# mainboard.net
KiCad netlist of a schematic drawn in EAGLE
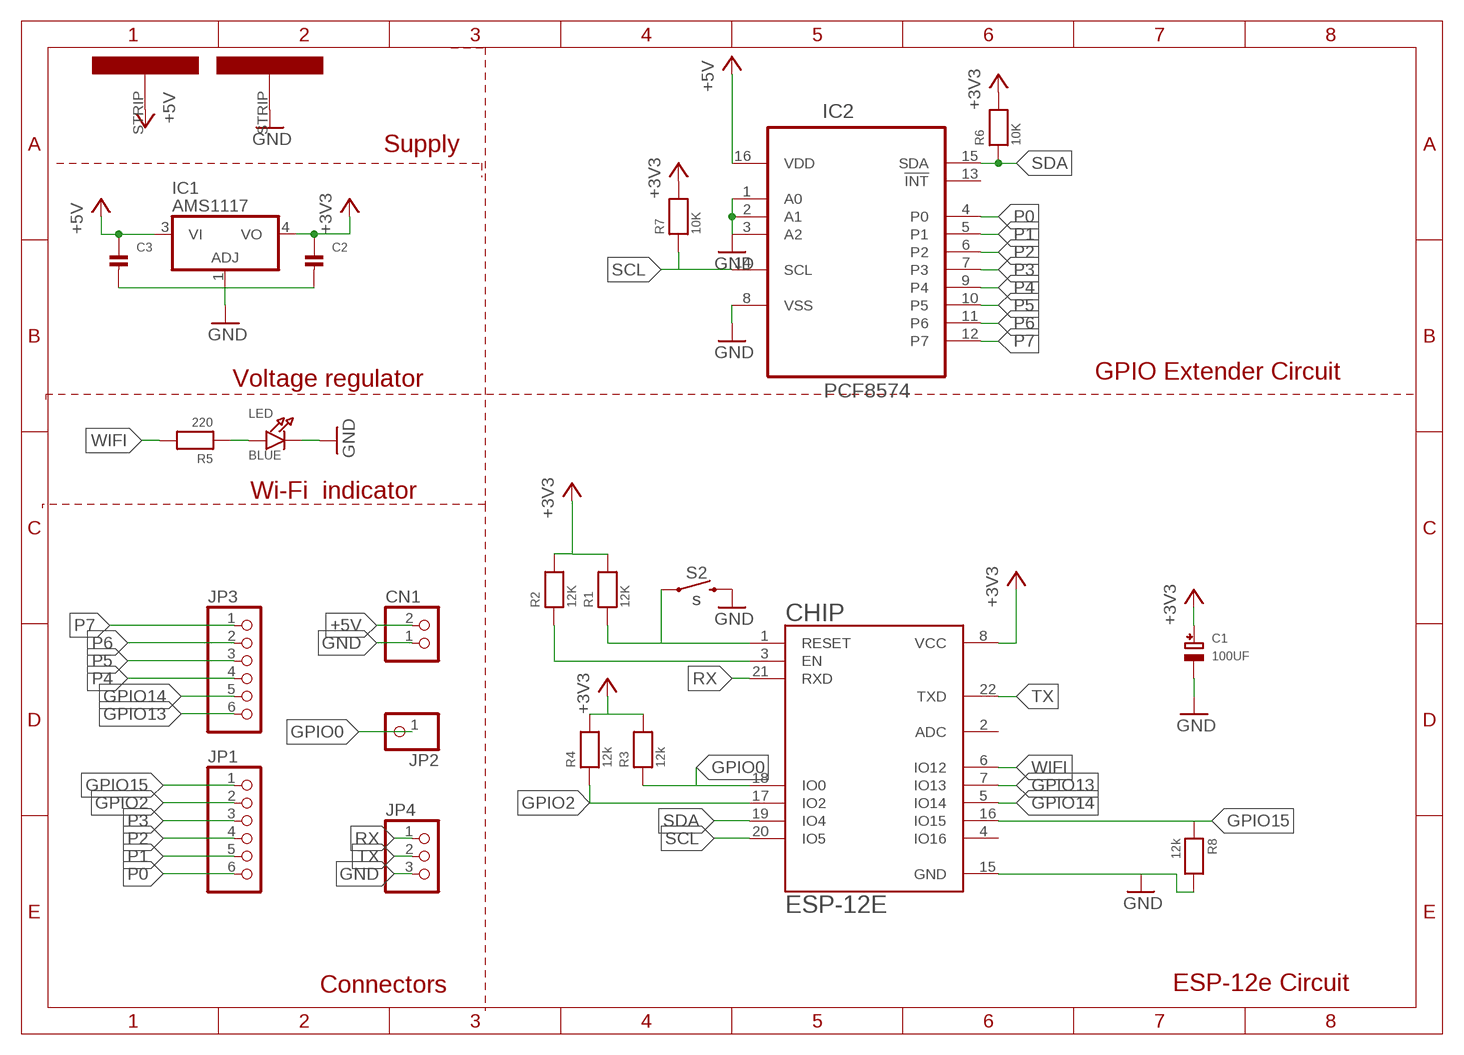
[diagram p0: schematic, sheet 1]
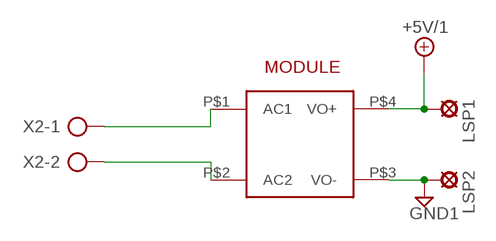
[diagram p1: schematic, sheet 2]

(export (version "E")
  (design (tool "Eeschema 10.0.6"))
  (components
    (comp (ref "C1")
      (value "100UF")
      (footprint "eagle-import:EIA6032-28_C-W")
      (libsource (lib "eagle-import") (part "CAP_TANTALUMC/6032_WAVE"))
    )
    (comp (ref "C2")
      (value "CAP_CERAMIC0805")
      (footprint "eagle-import:0805")
      (libsource (lib "eagle-import") (part "CAP_CERAMIC0805"))
    )
    (comp (ref "C3")
      (value "CAP_CERAMIC0805")
      (footprint "eagle-import:0805")
      (libsource (lib "eagle-import") (part "CAP_CERAMIC0805"))
    )
    (comp (ref "CHIP")
      (value "ESP-12E")
      (footprint "eagle-import:XCVR_ESP8266-12E_ESP-12E")
      (fields (field (name "MF") "AI-Thinker") (field (name "MP") "ESP8266-12E/ESP-12E"))
      (libsource (lib "eagle-import") (part "ESP8266-12E/ESP-12E"))
    )
    (comp (ref "CN1")
      (value "JST_2PIN-THM")
      (footprint "eagle-import:JST-PH-2-THM")
      (libsource (lib "eagle-import") (part "JST_2PIN-THM"))
    )
    (comp (ref "IC1")
      (value "AMS1117")
      (footprint "eagle-import:SOT223")
      (libsource (lib "eagle-import") (part "317EMP"))
    )
    (comp (ref "IC2")
      (value "PCF8574")
      (footprint "eagle-import:SOIC127P1032X265-16N")
      (fields
        (field (name "DIGI-KEY_PART_NUMBER") "568-1074-1-ND")
        (field (name "MF") "NXP USA")
        (field (name "MP") "PCF8574AT/3,518")
      )
      (libsource (lib "eagle-import") (part "PCF8574AT/3,518"))
    )
    (comp (ref "JP1")
      (value "PINHD-1X6CB")
      (footprint "eagle-import:1X06-CLEANBIG")
      (libsource (lib "eagle-import") (part "PINHD-1X6CB"))
    )
    (comp (ref "JP2")
      (value "PINHD-1X1CB")
      (footprint "eagle-import:1X01-CLEANBIG")
      (libsource (lib "eagle-import") (part "PINHD-1X1CB"))
    )
    (comp (ref "JP3")
      (value "PINHD-1X6CB")
      (footprint "eagle-import:1X06-CLEANBIG")
      (libsource (lib "eagle-import") (part "PINHD-1X6CB"))
    )
    (comp (ref "JP4")
      (value "PINHD-1X3CB")
      (footprint "eagle-import:1X03-CLEANBIG")
      (libsource (lib "eagle-import") (part "PINHD-1X3CB"))
    )
    (comp (ref "LED")
      (value "BLUE")
      (footprint "eagle-import:CHIPLED_0805")
      (libsource (lib "eagle-import") (part "LED0805"))
    )
    (comp (ref "R1")
      (value "12K")
      (footprint "eagle-import:0805")
      (libsource (lib "eagle-import") (part "RESISTOR0805"))
    )
    (comp (ref "R2")
      (value "12K")
      (footprint "eagle-import:0805")
      (libsource (lib "eagle-import") (part "RESISTOR0805"))
    )
    (comp (ref "R3")
      (value "12k")
      (footprint "eagle-import:0805")
      (libsource (lib "eagle-import") (part "RESISTOR0805"))
    )
    (comp (ref "R4")
      (value "12k")
      (footprint "eagle-import:0805")
      (libsource (lib "eagle-import") (part "RESISTOR0805"))
    )
    (comp (ref "R5")
      (value "220")
      (footprint "eagle-import:0805")
      (libsource (lib "eagle-import") (part "RESISTOR0805"))
    )
    (comp (ref "R6")
      (value "10K")
      (footprint "eagle-import:0805")
      (libsource (lib "eagle-import") (part "RESISTOR0805"))
    )
    (comp (ref "R7")
      (value "10K")
      (footprint "eagle-import:0805")
      (libsource (lib "eagle-import") (part "RESISTOR0805"))
    )
    (comp (ref "R8")
      (value "12k")
      (footprint "eagle-import:0805")
      (libsource (lib "eagle-import") (part "RESISTOR0805"))
    )
    (comp (ref "RAIL1")
      (value "RAIL1")
      (footprint "eagle-import:STRIP")
      (libsource (lib "eagle-import") (part "STRIP"))
    )
    (comp (ref "RAIL2")
      (value "RAIL2")
      (footprint "eagle-import:STRIP")
      (libsource (lib "eagle-import") (part "STRIP"))
    )
    (comp (ref "S2")
      (value "s")
      (footprint "eagle-import:TACTILE_SWITCH_PTH_6.0MM_KIT")
      (libsource (lib "eagle-import") (part "MOMENTARY-SWITCH-SPST-PTH-6.0MM-KIT"))
    )
    (comp (ref "LSP1")
      (value "LSP10")
      (footprint "eagle-import:LSP10")
      (libsource (lib "eagle-import") (part "LSP10"))
    )
    (comp (ref "LSP2")
      (value "LSP10")
      (footprint "eagle-import:LSP10")
      (libsource (lib "eagle-import") (part "LSP10"))
    )
    (comp (ref "MODULE")
      (value "HLK-PM01")
      (footprint "eagle-import:HLK-PM01")
      (fields (field (name "MF") "Hi-link") (field (name "MP") "hlk-pm01"))
      (libsource (lib "eagle-import") (part "HLK-PM01"))
    )
    (comp (ref "X2")
      (value "AK500/2-H")
      (footprint "eagle-import:AK500_2-H")
      (libsource (lib "eagle-import") (part "AK500/2-H"))
    )
  )
  (nets
    (net (code "1") (name "+3V3") (class "Default")
      (node (ref "C1") (pin "+") (pinfunction "+_+") (pintype "passive"))
      (node (ref "C2") (pin "1") (pinfunction "P$1_1") (pintype "passive"))
      (node (ref "CHIP") (pin "8") (pinfunction "VCC_8") (pintype "power_in"))
      (node (ref "IC1") (pin "4") (pinfunction "VO_4") (pintype "passive"))
      (node (ref "R1") (pin "2") (pinfunction "2_2") (pintype "passive"))
      (node (ref "R2") (pin "2") (pinfunction "2_2") (pintype "passive"))
      (node (ref "R3") (pin "2") (pinfunction "2_2") (pintype "passive"))
      (node (ref "R4") (pin "2") (pinfunction "2_2") (pintype "passive"))
      (node (ref "R6") (pin "2") (pinfunction "2_2") (pintype "passive"))
      (node (ref "R7") (pin "2") (pinfunction "2_2") (pintype "passive"))
    )
    (net (code "2") (name "+5V") (class "Default")
      (node (ref "C3") (pin "1") (pinfunction "P$1_1") (pintype "passive"))
      (node (ref "CN1") (pin "2") (pinfunction "1_2") (pintype "passive"))
      (node (ref "IC1") (pin "3") (pinfunction "VI_3") (pintype "input"))
      (node (ref "IC2") (pin "16") (pinfunction "VDD_16") (pintype "power_in"))
      (node (ref "RAIL1") (pin "STRIP") (pinfunction "STRIP_STRIP") (pintype "bidirectional"))
    )
    (net (code "3") (name "+5V{slash}1") (class "Default")
      (node (ref "LSP1") (pin "MP") (pinfunction "MP_MP") (pintype "passive"))
      (node (ref "MODULE") (pin "P$4") (pinfunction "VO+_P$4") (pintype "power_in"))
    )
    (net (code "4") (name "GND") (class "Default")
      (node (ref "C1") (pin "-") (pinfunction "-_-") (pintype "passive"))
      (node (ref "C2") (pin "2") (pinfunction "P$2_2") (pintype "passive"))
      (node (ref "C3") (pin "2") (pinfunction "P$2_2") (pintype "passive"))
      (node (ref "CHIP") (pin "15") (pinfunction "GND_15") (pintype "power_in"))
      (node (ref "CN1") (pin "1") (pinfunction "2_1") (pintype "passive"))
      (node (ref "IC1") (pin "1") (pinfunction "ADJ_1") (pintype "input"))
      (node (ref "IC2") (pin "1") (pinfunction "A0_1") (pintype "input"))
      (node (ref "IC2") (pin "2") (pinfunction "A1_2") (pintype "input"))
      (node (ref "IC2") (pin "3") (pinfunction "A2_3") (pintype "input"))
      (node (ref "IC2") (pin "8") (pinfunction "VSS_8") (pintype "passive"))
      (node (ref "JP4") (pin "3") (pinfunction "3_3") (pintype "passive"))
      (node (ref "LED") (pin "C") (pinfunction "C_C") (pintype "passive"))
      (node (ref "R8") (pin "2") (pinfunction "2_2") (pintype "passive"))
      (node (ref "RAIL2") (pin "STRIP") (pinfunction "STRIP_STRIP") (pintype "bidirectional"))
      (node (ref "S2") (pin "3") (pinfunction "2_3") (pintype "passive"))
    )
    (net (code "5") (name "GND1") (class "Default")
      (node (ref "LSP2") (pin "MP") (pinfunction "MP_MP") (pintype "passive"))
      (node (ref "MODULE") (pin "P$3") (pinfunction "VO-_P$3") (pintype "power_in"))
    )
    (net (code "6") (name "GPIO0") (class "Default")
      (node (ref "CHIP") (pin "18") (pinfunction "IO0_18") (pintype "bidirectional"))
      (node (ref "JP2") (pin "1") (pinfunction "1_1") (pintype "passive"))
      (node (ref "R3") (pin "1") (pinfunction "1_1") (pintype "passive"))
    )
    (net (code "7") (name "GPIO2") (class "Default")
      (node (ref "CHIP") (pin "17") (pinfunction "IO2_17") (pintype "bidirectional"))
      (node (ref "JP1") (pin "2") (pinfunction "2_2") (pintype "passive"))
      (node (ref "R4") (pin "1") (pinfunction "1_1") (pintype "passive"))
    )
    (net (code "8") (name "GPIO13") (class "Default")
      (node (ref "CHIP") (pin "7") (pinfunction "IO13_7") (pintype "bidirectional"))
      (node (ref "JP3") (pin "6") (pinfunction "6_6") (pintype "passive"))
    )
    (net (code "9") (name "GPIO14") (class "Default")
      (node (ref "CHIP") (pin "5") (pinfunction "IO14_5") (pintype "bidirectional"))
      (node (ref "JP3") (pin "5") (pinfunction "5_5") (pintype "passive"))
    )
    (net (code "10") (name "GPIO15") (class "Default")
      (node (ref "CHIP") (pin "16") (pinfunction "IO15_16") (pintype "bidirectional"))
      (node (ref "JP1") (pin "1") (pinfunction "1_1") (pintype "passive"))
      (node (ref "R8") (pin "1") (pinfunction "1_1") (pintype "passive"))
    )
    (net (code "11") (name "Net-(CHIP-EN)") (class "Default")
      (node (ref "CHIP") (pin "3") (pinfunction "EN_3") (pintype "input"))
      (node (ref "R2") (pin "1") (pinfunction "1_1") (pintype "passive"))
    )
    (net (code "12") (name "Net-(CHIP-RESET)") (class "Default")
      (node (ref "CHIP") (pin "1") (pinfunction "RESET_1") (pintype "input"))
      (node (ref "R1") (pin "1") (pinfunction "1_1") (pintype "passive"))
      (node (ref "S2") (pin "1") (pinfunction "1_1") (pintype "passive"))
    )
    (net (code "13") (name "Net-(LED-PadA)") (class "Default")
      (node (ref "LED") (pin "A") (pinfunction "A_A") (pintype "passive"))
      (node (ref "R5") (pin "1") (pinfunction "1_1") (pintype "passive"))
    )
    (net (code "14") (name "Net-(MODULE-AC1)") (class "Default")
      (node (ref "MODULE") (pin "P$1") (pinfunction "AC1_P$1") (pintype "input"))
      (node (ref "X2") (pin "1") (pinfunction "KL_1") (pintype "passive"))
    )
    (net (code "15") (name "Net-(MODULE-AC2)") (class "Default")
      (node (ref "MODULE") (pin "P$2") (pinfunction "AC2_P$2") (pintype "input"))
      (node (ref "X2") (pin "2") (pinfunction "KL_2") (pintype "passive"))
    )
    (net (code "16") (name "P0") (class "Default")
      (node (ref "IC2") (pin "4") (pinfunction "P0_4") (pintype "bidirectional"))
      (node (ref "JP1") (pin "6") (pinfunction "6_6") (pintype "passive"))
    )
    (net (code "17") (name "P1") (class "Default")
      (node (ref "IC2") (pin "5") (pinfunction "P1_5") (pintype "bidirectional"))
      (node (ref "JP1") (pin "5") (pinfunction "5_5") (pintype "passive"))
    )
    (net (code "18") (name "P2") (class "Default")
      (node (ref "IC2") (pin "6") (pinfunction "P2_6") (pintype "bidirectional"))
      (node (ref "JP1") (pin "4") (pinfunction "4_4") (pintype "passive"))
    )
    (net (code "19") (name "P3") (class "Default")
      (node (ref "IC2") (pin "7") (pinfunction "P3_7") (pintype "bidirectional"))
      (node (ref "JP1") (pin "3") (pinfunction "3_3") (pintype "passive"))
    )
    (net (code "20") (name "P4") (class "Default")
      (node (ref "IC2") (pin "9") (pinfunction "P4_9") (pintype "bidirectional"))
      (node (ref "JP3") (pin "4") (pinfunction "4_4") (pintype "passive"))
    )
    (net (code "21") (name "P5") (class "Default")
      (node (ref "IC2") (pin "10") (pinfunction "P5_10") (pintype "bidirectional"))
      (node (ref "JP3") (pin "3") (pinfunction "3_3") (pintype "passive"))
    )
    (net (code "22") (name "P6") (class "Default")
      (node (ref "IC2") (pin "11") (pinfunction "P6_11") (pintype "bidirectional"))
      (node (ref "JP3") (pin "2") (pinfunction "2_2") (pintype "passive"))
    )
    (net (code "23") (name "P7") (class "Default")
      (node (ref "IC2") (pin "12") (pinfunction "P7_12") (pintype "bidirectional"))
      (node (ref "JP3") (pin "1") (pinfunction "1_1") (pintype "passive"))
    )
    (net (code "24") (name "RX") (class "Default")
      (node (ref "CHIP") (pin "21") (pinfunction "RXD_21") (pintype "input"))
      (node (ref "JP4") (pin "1") (pinfunction "1_1") (pintype "passive"))
    )
    (net (code "25") (name "SCL") (class "Default")
      (node (ref "CHIP") (pin "20") (pinfunction "IO5_20") (pintype "bidirectional"))
      (node (ref "IC2") (pin "14") (pinfunction "SCL_14") (pintype "input"))
      (node (ref "R7") (pin "1") (pinfunction "1_1") (pintype "passive"))
    )
    (net (code "26") (name "SDA") (class "Default")
      (node (ref "CHIP") (pin "19") (pinfunction "IO4_19") (pintype "bidirectional"))
      (node (ref "IC2") (pin "15") (pinfunction "SDA_15") (pintype "bidirectional"))
      (node (ref "R6") (pin "1") (pinfunction "1_1") (pintype "passive"))
    )
    (net (code "27") (name "TX") (class "Default")
      (node (ref "CHIP") (pin "22") (pinfunction "TXD_22") (pintype "output"))
      (node (ref "JP4") (pin "2") (pinfunction "2_2") (pintype "passive"))
    )
    (net (code "28") (name "WIFI") (class "Default")
      (node (ref "CHIP") (pin "6") (pinfunction "IO12_6") (pintype "bidirectional"))
      (node (ref "R5") (pin "2") (pinfunction "2_2") (pintype "passive"))
    )
    (net (code "29") (name "unconnected-(CHIP-ADC-Pad2)") (class "Default")
      (node (ref "CHIP") (pin "2") (pinfunction "ADC_2") (pintype "passive"))
    )
    (net (code "30") (name "unconnected-(CHIP-IO16-Pad4)") (class "Default")
      (node (ref "CHIP") (pin "4") (pinfunction "IO16_4") (pintype "bidirectional"))
    )
    (net (code "31") (name "unconnected-(IC2-~{INT}-Pad13)") (class "Default")
      (node (ref "IC2") (pin "13") (pinfunction "~{INT}_13") (pintype "output"))
    )
  )
)
